# relay.net
KiCad netlist of a schematic drawn in EAGLE
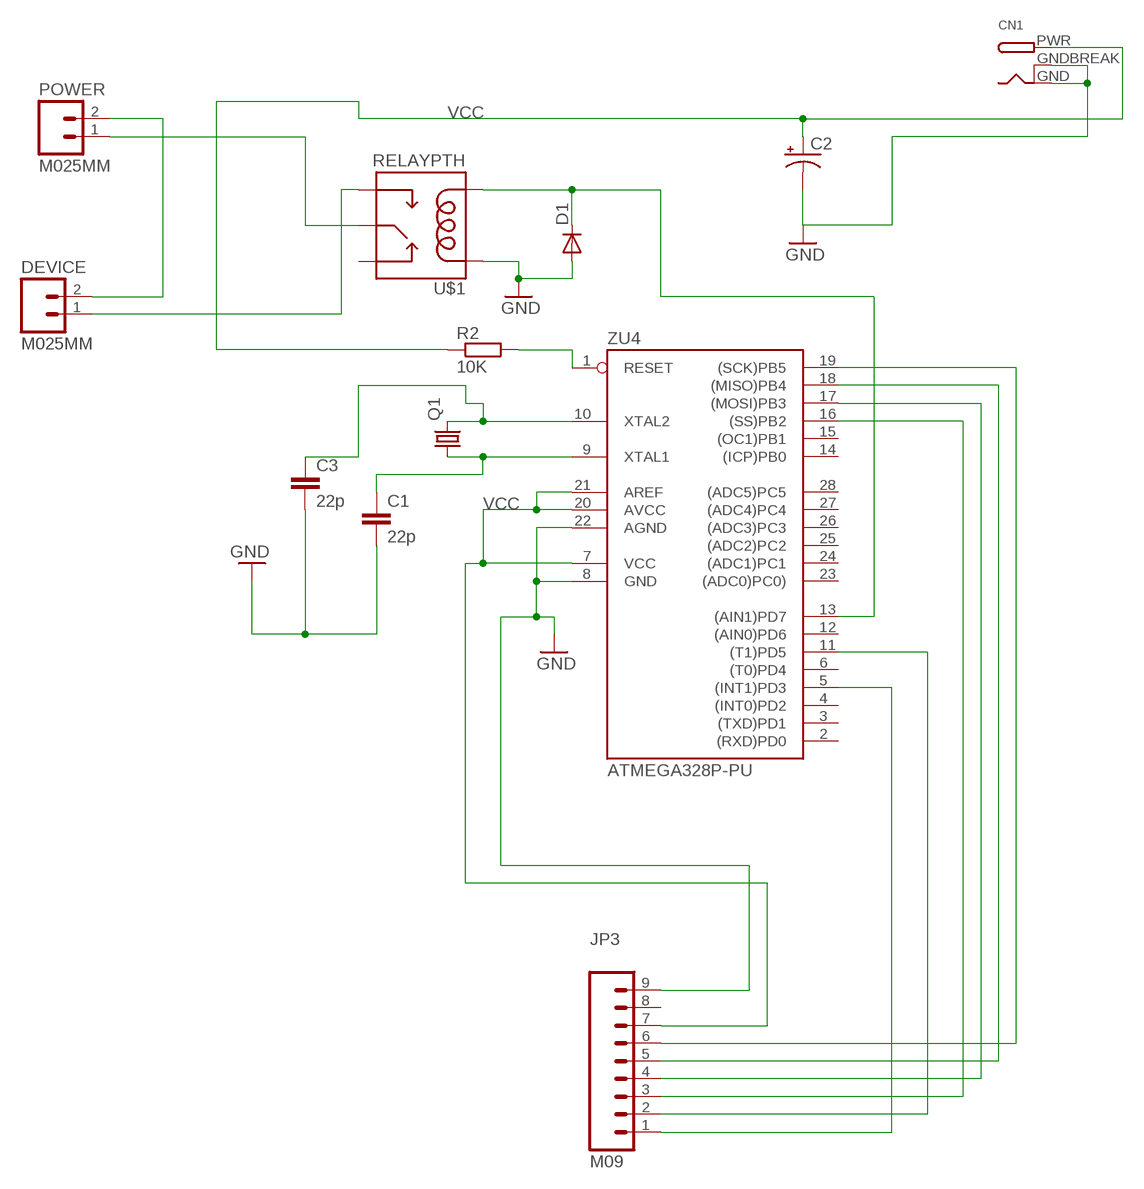
[diagram p0: schematic, sheet 1]

(export (version "E")
  (design (tool "Eeschema 10.0.6"))
  (components
    (comp (ref "C1")
      (value "22p")
      (footprint "eagle-import:C050-025X075")
      (libsource (lib "eagle-import") (part "C-EU050-025X075"))
    )
    (comp (ref "C2")
      (value "CAP_POLPTH1")
      (footprint "eagle-import:CPOL-RADIAL-100UF-25V")
      (libsource (lib "eagle-import") (part "CAP_POLPTH1"))
    )
    (comp (ref "C3")
      (value "22p")
      (footprint "eagle-import:C050-025X075")
      (libsource (lib "eagle-import") (part "C-EU050-025X075"))
    )
    (comp (ref "CN1")
      (value "DCBARRELPTH")
      (footprint "eagle-import:DCJACK_2MM_PTH")
      (libsource (lib "eagle-import") (part "DCBARRELPTH"))
    )
    (comp (ref "D1")
      (value "DIODE1N4148")
      (footprint "eagle-import:DIODE-1N4148")
      (libsource (lib "eagle-import") (part "DIODE1N4148"))
    )
    (comp (ref "DEVICE")
      (value "M025MM")
      (footprint "eagle-import:SCREWTERMINAL-5MM-2")
      (libsource (lib "eagle-import") (part "M025MM"))
    )
    (comp (ref "JP3")
      (value "M09")
      (footprint "eagle-import:1X09")
      (libsource (lib "eagle-import") (part "M09"))
    )
    (comp (ref "POWER")
      (value "M025MM")
      (footprint "eagle-import:SCREWTERMINAL-5MM-2")
      (libsource (lib "eagle-import") (part "M025MM"))
    )
    (comp (ref "Q1")
      (value "CRYSTALHC49S")
      (footprint "eagle-import:HC49_S")
      (libsource (lib "eagle-import") (part "CRYSTALHC49S"))
    )
    (comp (ref "R2")
      (value "10K")
      (footprint "eagle-import:0207_7")
      (libsource (lib "eagle-import") (part "R-EU_0207/7"))
    )
    (comp (ref "U$1")
      (value "RELAYPTH")
      (footprint "eagle-import:RELAY-G5Q")
      (libsource (lib "eagle-import") (part "RELAYPTH"))
    )
    (comp (ref "ZU4")
      (value "ATMEGA328P-PU")
      (footprint "eagle-import:DIL28-3")
      (libsource (lib "eagle-import") (part "ATMEGA328P-PU"))
    )
  )
  (nets
    (net (code "1") (name "/VCC") (class "Default")
      (node (ref "C2") (pin "1") (pinfunction "+_1") (pintype "passive"))
      (node (ref "CN1") (pin "PWR") (pinfunction "PWR_PWR") (pintype "power_in"))
      (node (ref "JP3") (pin "7") (pinfunction "7_7") (pintype "passive"))
      (node (ref "R2") (pin "1") (pinfunction "1_1") (pintype "passive"))
      (node (ref "ZU4") (pin "20") (pinfunction "AVCC_20") (pintype "power_in"))
      (node (ref "ZU4") (pin "21") (pinfunction "AREF_21") (pintype "passive"))
      (node (ref "ZU4") (pin "7") (pinfunction "VCC_7") (pintype "power_in"))
    )
    (net (code "2") (name "GND") (class "Default")
      (node (ref "C1") (pin "2") (pinfunction "2_2") (pintype "passive"))
      (node (ref "C2") (pin "2") (pinfunction "-_2") (pintype "passive"))
      (node (ref "C3") (pin "2") (pinfunction "2_2") (pintype "passive"))
      (node (ref "CN1") (pin "GND") (pinfunction "GND_GND") (pintype "power_in"))
      (node (ref "CN1") (pin "GNDBREAK") (pinfunction "GNDBREAK_GNDBREAK") (pintype "power_in"))
      (node (ref "D1") (pin "A") (pinfunction "A_A") (pintype "passive"))
      (node (ref "JP3") (pin "9") (pinfunction "9_9") (pintype "passive"))
      (node (ref "U$1") (pin "5") (pinfunction "COIL1_5") (pintype "bidirectional"))
      (node (ref "ZU4") (pin "22") (pinfunction "AGND_22") (pintype "power_in"))
      (node (ref "ZU4") (pin "8") (pinfunction "GND_8") (pintype "power_in"))
    )
    (net (code "3") (name "Net-(DEVICE-Pad2)") (class "Default")
      (node (ref "DEVICE") (pin "2") (pinfunction "2_2") (pintype "passive"))
      (node (ref "POWER") (pin "2") (pinfunction "2_2") (pintype "passive"))
    )
    (net (code "4") (name "Net-(U$1-COIL2)") (class "Default")
      (node (ref "D1") (pin "C") (pinfunction "C_C") (pintype "passive"))
      (node (ref "U$1") (pin "1") (pinfunction "COIL2_1") (pintype "bidirectional"))
      (node (ref "ZU4") (pin "13") (pinfunction "(AIN1)PD7_13") (pintype "bidirectional"))
    )
    (net (code "5") (name "Net-(U$1-MAIN)") (class "Default")
      (node (ref "POWER") (pin "1") (pinfunction "1_1") (pintype "passive"))
      (node (ref "U$1") (pin "2") (pinfunction "MAIN_2") (pintype "bidirectional"))
    )
    (net (code "6") (name "Net-(U$1-NO)") (class "Default")
      (node (ref "DEVICE") (pin "1") (pinfunction "1_1") (pintype "passive"))
      (node (ref "U$1") (pin "3") (pinfunction "NO_3") (pintype "bidirectional"))
    )
    (net (code "7") (name "Net-(ZU4-(INT1)PD3)") (class "Default")
      (node (ref "JP3") (pin "1") (pinfunction "1_1") (pintype "passive"))
      (node (ref "ZU4") (pin "5") (pinfunction "(INT1)PD3_5") (pintype "bidirectional"))
    )
    (net (code "8") (name "Net-(ZU4-(MISO)PB4)") (class "Default")
      (node (ref "JP3") (pin "5") (pinfunction "5_5") (pintype "passive"))
      (node (ref "ZU4") (pin "18") (pinfunction "(MISO)PB4_18") (pintype "bidirectional"))
    )
    (net (code "9") (name "Net-(ZU4-(MOSI)PB3)") (class "Default")
      (node (ref "JP3") (pin "4") (pinfunction "4_4") (pintype "passive"))
      (node (ref "ZU4") (pin "17") (pinfunction "(MOSI)PB3_17") (pintype "bidirectional"))
    )
    (net (code "10") (name "Net-(ZU4-(SCK)PB5)") (class "Default")
      (node (ref "JP3") (pin "6") (pinfunction "6_6") (pintype "passive"))
      (node (ref "ZU4") (pin "19") (pinfunction "(SCK)PB5_19") (pintype "bidirectional"))
    )
    (net (code "11") (name "Net-(ZU4-(SS)PB2)") (class "Default")
      (node (ref "JP3") (pin "3") (pinfunction "3_3") (pintype "passive"))
      (node (ref "ZU4") (pin "16") (pinfunction "(SS)PB2_16") (pintype "bidirectional"))
    )
    (net (code "12") (name "Net-(ZU4-(T1)PD5)") (class "Default")
      (node (ref "JP3") (pin "2") (pinfunction "2_2") (pintype "passive"))
      (node (ref "ZU4") (pin "11") (pinfunction "(T1)PD5_11") (pintype "bidirectional"))
    )
    (net (code "13") (name "Net-(ZU4-RESET)") (class "Default")
      (node (ref "R2") (pin "2") (pinfunction "2_2") (pintype "passive"))
      (node (ref "ZU4") (pin "1") (pinfunction "RESET_1") (pintype "input"))
    )
    (net (code "14") (name "Net-(ZU4-XTAL1)") (class "Default")
      (node (ref "C1") (pin "1") (pinfunction "1_1") (pintype "passive"))
      (node (ref "Q1") (pin "1") (pinfunction "1_1") (pintype "passive"))
      (node (ref "ZU4") (pin "9") (pinfunction "XTAL1_9") (pintype "bidirectional"))
    )
    (net (code "15") (name "Net-(ZU4-XTAL2)") (class "Default")
      (node (ref "C3") (pin "1") (pinfunction "1_1") (pintype "passive"))
      (node (ref "Q1") (pin "2") (pinfunction "2_2") (pintype "passive"))
      (node (ref "ZU4") (pin "10") (pinfunction "XTAL2_10") (pintype "bidirectional"))
    )
    (net (code "16") (name "unconnected-(JP3-Pad8)") (class "Default")
      (node (ref "JP3") (pin "8") (pinfunction "8_8") (pintype "passive"))
    )
    (net (code "17") (name "unconnected-(U$1-NC-Pad4)") (class "Default")
      (node (ref "U$1") (pin "4") (pinfunction "NC_4") (pintype "bidirectional"))
    )
    (net (code "18") (name "unconnected-(ZU4-(ADC0)PC0)-Pad23)") (class "Default")
      (node (ref "ZU4") (pin "23") (pinfunction "(ADC0)PC0)_23") (pintype "bidirectional"))
    )
    (net (code "19") (name "unconnected-(ZU4-(ADC1)PC1-Pad24)") (class "Default")
      (node (ref "ZU4") (pin "24") (pinfunction "(ADC1)PC1_24") (pintype "bidirectional"))
    )
    (net (code "20") (name "unconnected-(ZU4-(ADC2)PC2-Pad25)") (class "Default")
      (node (ref "ZU4") (pin "25") (pinfunction "(ADC2)PC2_25") (pintype "bidirectional"))
    )
    (net (code "21") (name "unconnected-(ZU4-(ADC3)PC3-Pad26)") (class "Default")
      (node (ref "ZU4") (pin "26") (pinfunction "(ADC3)PC3_26") (pintype "bidirectional"))
    )
    (net (code "22") (name "unconnected-(ZU4-(ADC4)PC4-Pad27)") (class "Default")
      (node (ref "ZU4") (pin "27") (pinfunction "(ADC4)PC4_27") (pintype "bidirectional"))
    )
    (net (code "23") (name "unconnected-(ZU4-(ADC5)PC5-Pad28)") (class "Default")
      (node (ref "ZU4") (pin "28") (pinfunction "(ADC5)PC5_28") (pintype "bidirectional"))
    )
    (net (code "24") (name "unconnected-(ZU4-(AIN0)PD6-Pad12)") (class "Default")
      (node (ref "ZU4") (pin "12") (pinfunction "(AIN0)PD6_12") (pintype "bidirectional"))
    )
    (net (code "25") (name "unconnected-(ZU4-(ICP)PB0-Pad14)") (class "Default")
      (node (ref "ZU4") (pin "14") (pinfunction "(ICP)PB0_14") (pintype "bidirectional"))
    )
    (net (code "26") (name "unconnected-(ZU4-(INT0)PD2-Pad4)") (class "Default")
      (node (ref "ZU4") (pin "4") (pinfunction "(INT0)PD2_4") (pintype "bidirectional"))
    )
    (net (code "27") (name "unconnected-(ZU4-(OC1)PB1-Pad15)") (class "Default")
      (node (ref "ZU4") (pin "15") (pinfunction "(OC1)PB1_15") (pintype "bidirectional"))
    )
    (net (code "28") (name "unconnected-(ZU4-(RXD)PD0-Pad2)") (class "Default")
      (node (ref "ZU4") (pin "2") (pinfunction "(RXD)PD0_2") (pintype "bidirectional"))
    )
    (net (code "29") (name "unconnected-(ZU4-(T0)PD4-Pad6)") (class "Default")
      (node (ref "ZU4") (pin "6") (pinfunction "(T0)PD4_6") (pintype "bidirectional"))
    )
    (net (code "30") (name "unconnected-(ZU4-(TXD)PD1-Pad3)") (class "Default")
      (node (ref "ZU4") (pin "3") (pinfunction "(TXD)PD1_3") (pintype "bidirectional"))
    )
  )
)
